# imu_hand.net
KiCad netlist of a schematic drawn in EAGLE
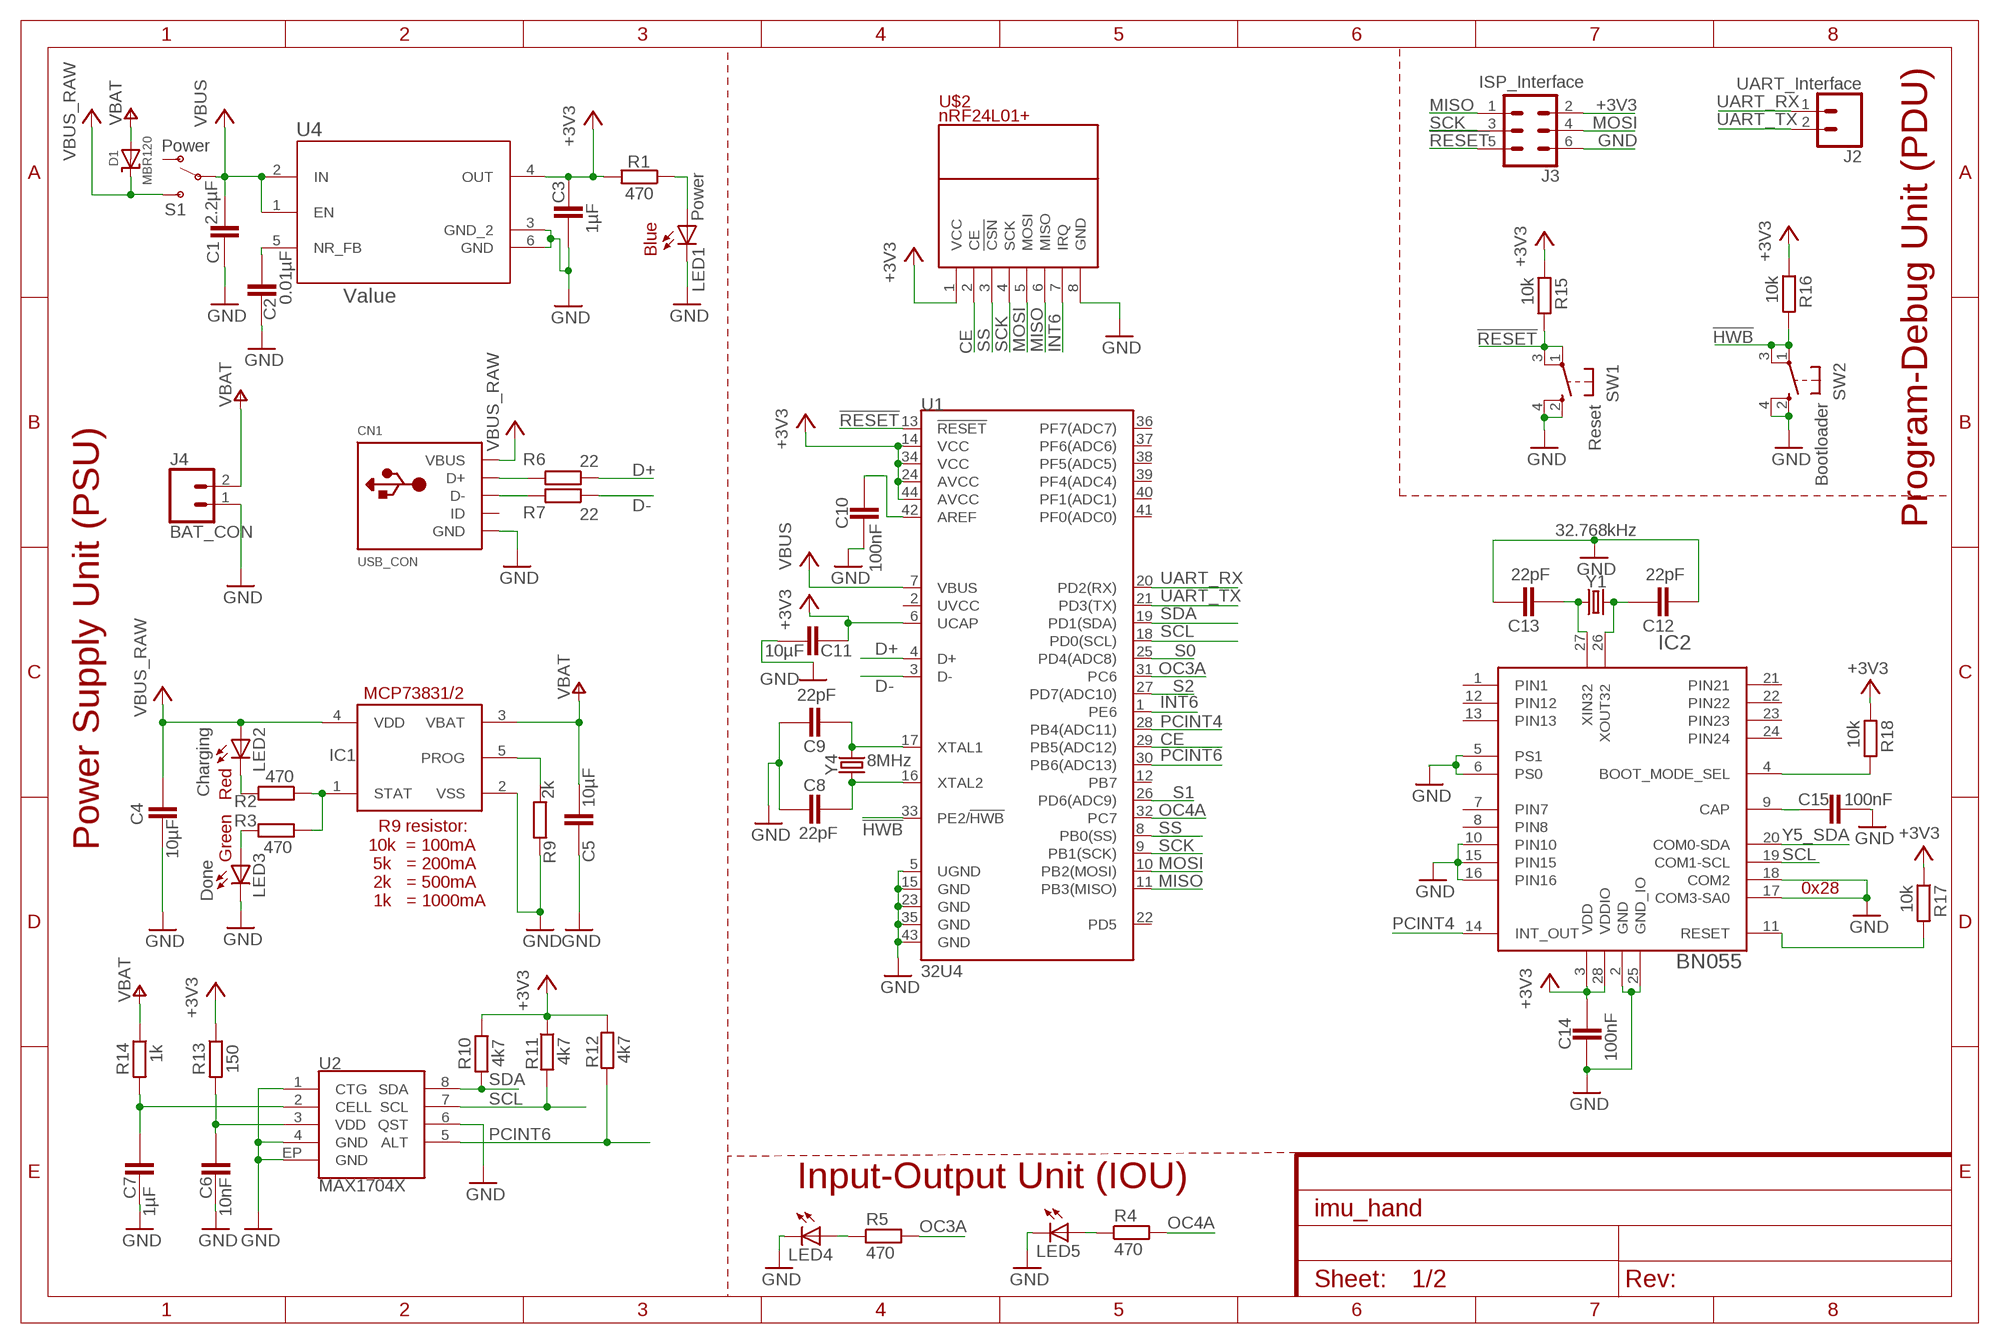
[diagram p0: schematic, sheet 1]
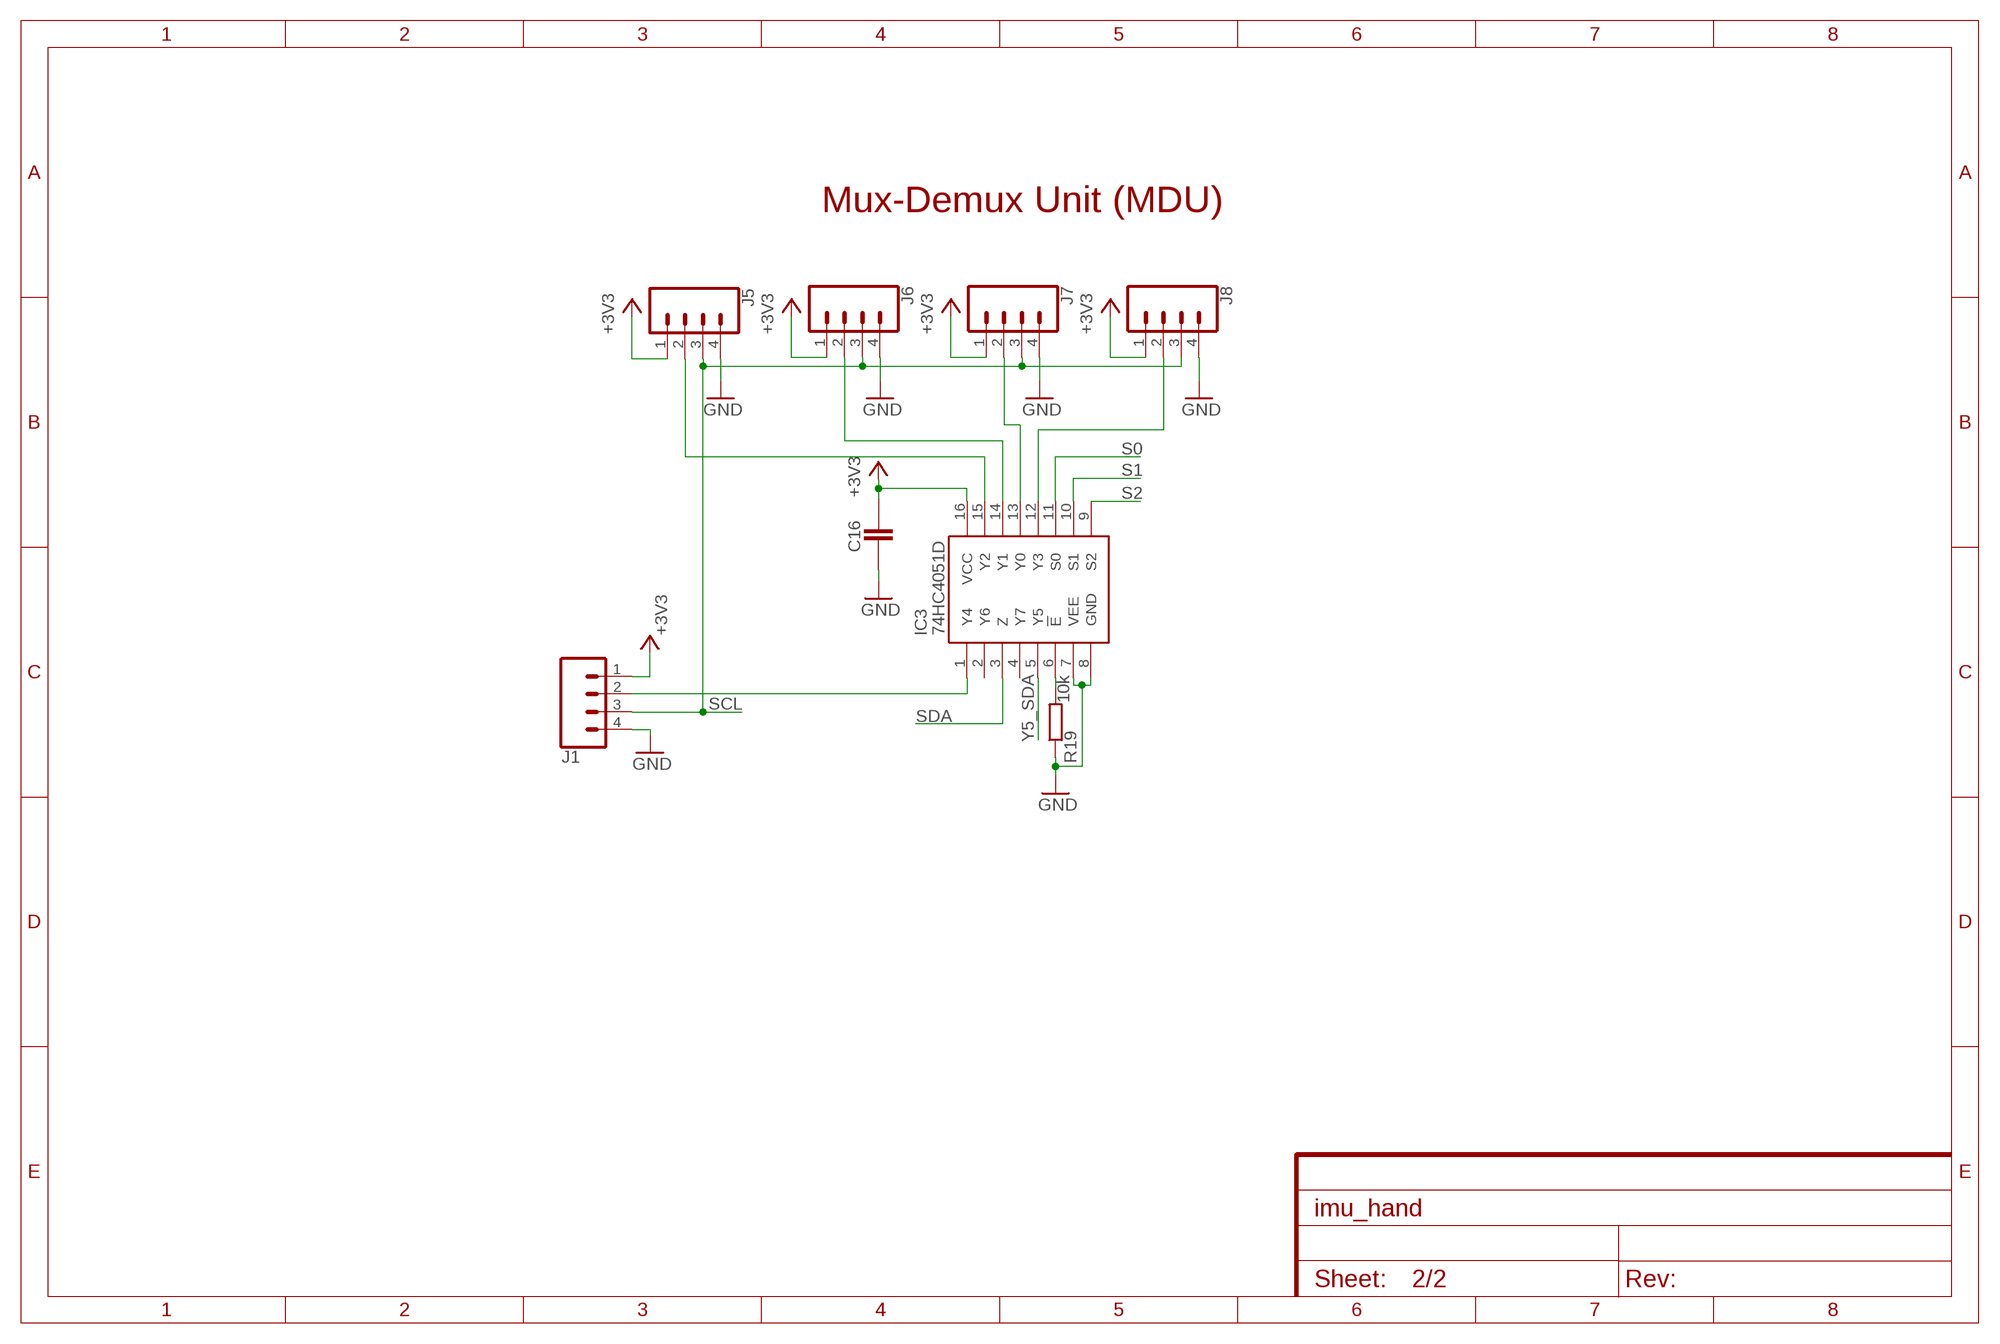
[diagram p1: schematic, sheet 2]

(export (version "E")
  (design (tool "Eeschema 10.0.6"))
  (components
    (comp (ref "C16")
      (value "CAPACITOR_0603")
      (footprint "eagle-import:CAPC1608X92N")
      (libsource (lib "eagle-import") (part "CAPACITOR_0603"))
    )
    (comp (ref "IC3")
      (value "74HC4051D")
      (footprint "eagle-import:SOIC127P600X175-16N")
      (fields (field (name "RS_PART_NUMBER") "1697756P"))
      (libsource (lib "eagle-import") (part "74HC4051D"))
    )
    (comp (ref "J1")
      (value "CONN_04SMD2")
      (footprint "eagle-import:1X04_1MM_RA")
      (libsource (lib "eagle-import") (part "CONN_04SMD2"))
    )
    (comp (ref "J5")
      (value "CONN_04SMD2")
      (footprint "eagle-import:1X04_1MM_RA")
      (libsource (lib "eagle-import") (part "CONN_04SMD2"))
    )
    (comp (ref "J6")
      (value "CONN_04SMD2")
      (footprint "eagle-import:1X04_1MM_RA")
      (libsource (lib "eagle-import") (part "CONN_04SMD2"))
    )
    (comp (ref "J7")
      (value "CONN_04SMD2")
      (footprint "eagle-import:1X04_1MM_RA")
      (libsource (lib "eagle-import") (part "CONN_04SMD2"))
    )
    (comp (ref "J8")
      (value "CONN_04SMD2")
      (footprint "eagle-import:1X04_1MM_RA")
      (libsource (lib "eagle-import") (part "CONN_04SMD2"))
    )
    (comp (ref "R19")
      (value "10k")
      (footprint "eagle-import:RESC1608X55N")
      (libsource (lib "eagle-import") (part "RESISTOR_0603"))
    )
    (comp (ref "C1")
      (value "2.2µF")
      (footprint "eagle-import:CAPC1608X92N")
      (libsource (lib "eagle-import") (part "CAPACITOR_0603"))
    )
    (comp (ref "C2")
      (value "0.01µF")
      (footprint "eagle-import:CAPC1608X92N")
      (libsource (lib "eagle-import") (part "CAPACITOR_0603"))
    )
    (comp (ref "C3")
      (value "1µF")
      (footprint "eagle-import:CAPC1608X92N")
      (libsource (lib "eagle-import") (part "CAPACITOR_0603"))
    )
    (comp (ref "C4")
      (value "10µF")
      (footprint "eagle-import:CAPC1608X92N")
      (libsource (lib "eagle-import") (part "CAPACITOR_0603"))
    )
    (comp (ref "C5")
      (value "10µF")
      (footprint "eagle-import:CAPC1608X92N")
      (libsource (lib "eagle-import") (part "CAPACITOR_0603"))
    )
    (comp (ref "C6")
      (value "10nF")
      (footprint "eagle-import:CAPC1608X92N")
      (libsource (lib "eagle-import") (part "CAPACITOR_0603"))
    )
    (comp (ref "C7")
      (value "1µF")
      (footprint "eagle-import:CAPC1608X92N")
      (libsource (lib "eagle-import") (part "CAPACITOR_0603"))
    )
    (comp (ref "C8")
      (value "22pF")
      (footprint "eagle-import:CAPC1608X92N")
      (libsource (lib "eagle-import") (part "CAPACITOR_0603"))
    )
    (comp (ref "C9")
      (value "22pF")
      (footprint "eagle-import:CAPC1608X92N")
      (libsource (lib "eagle-import") (part "CAPACITOR_0603"))
    )
    (comp (ref "C10")
      (value "100nF")
      (footprint "eagle-import:CAPC1608X92N")
      (libsource (lib "eagle-import") (part "CAPACITOR_0603"))
    )
    (comp (ref "C11")
      (value "10µF")
      (footprint "eagle-import:CAPC1608X92N")
      (libsource (lib "eagle-import") (part "CAPACITOR_0603"))
    )
    (comp (ref "C12")
      (value "22pF")
      (footprint "eagle-import:CAPC1608X92N")
      (libsource (lib "eagle-import") (part "CAPACITOR_0603"))
    )
    (comp (ref "C13")
      (value "22pF")
      (footprint "eagle-import:CAPC1608X92N")
      (libsource (lib "eagle-import") (part "CAPACITOR_0603"))
    )
    (comp (ref "C14")
      (value "100nF")
      (footprint "eagle-import:CAPC1608X92N")
      (libsource (lib "eagle-import") (part "CAPACITOR_0603"))
    )
    (comp (ref "C15")
      (value "100nF")
      (footprint "eagle-import:CAPC1608X92N")
      (libsource (lib "eagle-import") (part "CAPACITOR_0603"))
    )
    (comp (ref "CN1")
      (value "USB_CON")
      (footprint "eagle-import:USB-MINIB")
      (libsource (lib "eagle-import") (part "USBMINIB"))
    )
    (comp (ref "D1")
      (value "MBR120")
      (footprint "eagle-import:SOD-123FL")
      (libsource (lib "eagle-import") (part "DIODE_SOD-123FL"))
    )
    (comp (ref "IC1")
      (value "MCP73831/OT")
      (footprint "eagle-import:SOT23-5L")
      (libsource (lib "eagle-import") (part "MCP73831/OT"))
    )
    (comp (ref "IC2")
      (value "BN055")
      (footprint "eagle-import:LGA-28_3.80X5.20_0.5")
      (fields (field (name "PART_NUMBER") "BNO055"))
      (libsource (lib "eagle-import") (part "1658_BNO055"))
    )
    (comp (ref "J2")
      (value "UART_Interface")
      (footprint "eagle-import:1X02")
      (libsource (lib "eagle-import") (part "CONN_02"))
    )
    (comp (ref "J3")
      (value "ISP_Interface")
      (footprint "eagle-import:2X3")
      (libsource (lib "eagle-import") (part "CONN_03X2FEMALE"))
    )
    (comp (ref "J4")
      (value "BAT_CON")
      (footprint "eagle-import:1X02")
      (libsource (lib "eagle-import") (part "CONN_02"))
    )
    (comp (ref "LED1")
      (value "Power")
      (footprint "eagle-import:CHIPLED_0603")
      (libsource (lib "eagle-import") (part "LEDCHIPLED_0603"))
    )
    (comp (ref "LED2")
      (value "Charging")
      (footprint "eagle-import:CHIPLED_0603")
      (libsource (lib "eagle-import") (part "LEDCHIPLED_0603"))
    )
    (comp (ref "LED3")
      (value "Done")
      (footprint "eagle-import:CHIPLED_0603")
      (libsource (lib "eagle-import") (part "LEDCHIPLED_0603"))
    )
    (comp (ref "LED4")
      (value "LEDCHIPLED_0603")
      (footprint "eagle-import:CHIPLED_0603")
      (libsource (lib "eagle-import") (part "LEDCHIPLED_0603"))
    )
    (comp (ref "LED5")
      (value "LEDCHIPLED_0603")
      (footprint "eagle-import:CHIPLED_0603")
      (libsource (lib "eagle-import") (part "LEDCHIPLED_0603"))
    )
    (comp (ref "R1")
      (value "470")
      (footprint "eagle-import:RESC1608X55N")
      (libsource (lib "eagle-import") (part "RESISTOR_0603"))
    )
    (comp (ref "R2")
      (value "470")
      (footprint "eagle-import:RESC1608X55N")
      (libsource (lib "eagle-import") (part "RESISTOR_0603"))
    )
    (comp (ref "R3")
      (value "470")
      (footprint "eagle-import:RESC1608X55N")
      (libsource (lib "eagle-import") (part "RESISTOR_0603"))
    )
    (comp (ref "R4")
      (value "470")
      (footprint "eagle-import:RESC1608X55N")
      (libsource (lib "eagle-import") (part "RESISTOR_0603"))
    )
    (comp (ref "R5")
      (value "470")
      (footprint "eagle-import:RESC1608X55N")
      (libsource (lib "eagle-import") (part "RESISTOR_0603"))
    )
    (comp (ref "R6")
      (value "22")
      (footprint "eagle-import:RESC1608X55N")
      (libsource (lib "eagle-import") (part "RESISTOR_0603"))
    )
    (comp (ref "R7")
      (value "22")
      (footprint "eagle-import:RESC1608X55N")
      (libsource (lib "eagle-import") (part "RESISTOR_0603"))
    )
    (comp (ref "R9")
      (value "2k")
      (footprint "eagle-import:RESC1608X55N")
      (libsource (lib "eagle-import") (part "RESISTOR_0603"))
    )
    (comp (ref "R10")
      (value "4k7")
      (footprint "eagle-import:RESC1608X55N")
      (libsource (lib "eagle-import") (part "RESISTOR_0603"))
    )
    (comp (ref "R11")
      (value "4k7")
      (footprint "eagle-import:RESC1608X55N")
      (libsource (lib "eagle-import") (part "RESISTOR_0603"))
    )
    (comp (ref "R12")
      (value "4k7")
      (footprint "eagle-import:RESC1608X55N")
      (libsource (lib "eagle-import") (part "RESISTOR_0603"))
    )
    (comp (ref "R13")
      (value "150")
      (footprint "eagle-import:RESC1608X55N")
      (libsource (lib "eagle-import") (part "RESISTOR_0603"))
    )
    (comp (ref "R14")
      (value "1k")
      (footprint "eagle-import:RESC1608X55N")
      (libsource (lib "eagle-import") (part "RESISTOR_0603"))
    )
    (comp (ref "R15")
      (value "10k")
      (footprint "eagle-import:RESC1608X55N")
      (libsource (lib "eagle-import") (part "RESISTOR_0603"))
    )
    (comp (ref "R16")
      (value "10k")
      (footprint "eagle-import:RESC1608X55N")
      (libsource (lib "eagle-import") (part "RESISTOR_0603"))
    )
    (comp (ref "R17")
      (value "10k")
      (footprint "eagle-import:RESC1608X55N")
      (libsource (lib "eagle-import") (part "RESISTOR_0603"))
    )
    (comp (ref "R18")
      (value "10k")
      (footprint "eagle-import:RESC1608X55N")
      (libsource (lib "eagle-import") (part "RESISTOR_0603"))
    )
    (comp (ref "S1")
      (value "Power")
      (footprint "eagle-import:SWITCH_SPDT_PTH_11.6X4.0MM")
      (libsource (lib "eagle-import") (part "SWITCH-SPDT-PTH-11.6X4.0MM"))
    )
    (comp (ref "SW1")
      (value "Reset")
      (footprint "eagle-import:KMR2")
      (libsource (lib "eagle-import") (part "SPST_TACT-KMR2"))
    )
    (comp (ref "SW2")
      (value "Bootloader")
      (footprint "eagle-import:KMR2")
      (libsource (lib "eagle-import") (part "SPST_TACT-KMR2"))
    )
    (comp (ref "U$2")
      (value "nRF24L01+")
      (footprint "eagle-import:6-PIN-BREAKOUT")
      (libsource (lib "eagle-import") (part "6-PIN-BREAKOUT6-PIN-BREAKOUT"))
    )
    (comp (ref "U1")
      (value "32U4")
      (footprint "eagle-import:TQFP44")
      (libsource (lib "eagle-import") (part "ATMEGA32U4TQFP-44"))
    )
    (comp (ref "U2")
      (value "MAX1704X")
      (footprint "eagle-import:TDFN-8")
      (libsource (lib "eagle-import") (part "MAX1704X"))
    )
    (comp (ref "U4")
      (value "Value")
      (footprint "eagle-import:DCQ0006A_N")
      (fields (field (name "MANUFACTURER") "Texas Instruments") (field (name "PARTNUMBER") "TPS79633QDCQRQ1"))
      (libsource (lib "eagle-import") (part "TPS79633QDCQRQ1"))
    )
    (comp (ref "Y1")
      (value "32.768kHz")
      (footprint "eagle-import:CRYSTAL-SMD-3.2X1.5MM")
      (libsource (lib "eagle-import") (part "CRYSTAL-32.768KHZSMD-3.2X1.5"))
    )
    (comp (ref "Y4")
      (value "8MHz")
      (footprint "eagle-import:CRYSTAL-SMD-5X3.2-4PAD")
      (libsource (lib "eagle-import") (part "CRYSTAL-8MHZSMD-5X3.2"))
    )
  )
  (nets
    (net (code "1") (name "+3V3") (class "Default")
      (node (ref "C11") (pin "1") (pinfunction "1_1") (pintype "passive"))
      (node (ref "C14") (pin "1") (pinfunction "1_1") (pintype "passive"))
      (node (ref "C16") (pin "2") (pinfunction "2_2") (pintype "passive"))
      (node (ref "C3") (pin "2") (pinfunction "2_2") (pintype "passive"))
      (node (ref "IC2") (pin "28") (pinfunction "VDDIO_28") (pintype "power_in"))
      (node (ref "IC2") (pin "3") (pinfunction "VDD_3") (pintype "power_in"))
      (node (ref "IC3") (pin "16") (pinfunction "VCC_16") (pintype "bidirectional"))
      (node (ref "J1") (pin "1") (pinfunction "1_1") (pintype "passive"))
      (node (ref "J3") (pin "2") (pinfunction "2_2") (pintype "bidirectional"))
      (node (ref "J5") (pin "1") (pinfunction "1_1") (pintype "passive"))
      (node (ref "J6") (pin "1") (pinfunction "1_1") (pintype "passive"))
      (node (ref "J7") (pin "1") (pinfunction "1_1") (pintype "passive"))
      (node (ref "J8") (pin "1") (pinfunction "1_1") (pintype "passive"))
      (node (ref "R1") (pin "2") (pinfunction "2_2") (pintype "passive"))
      (node (ref "R10") (pin "1") (pinfunction "1_1") (pintype "passive"))
      (node (ref "R11") (pin "1") (pinfunction "1_1") (pintype "passive"))
      (node (ref "R12") (pin "1") (pinfunction "1_1") (pintype "passive"))
      (node (ref "R13") (pin "1") (pinfunction "1_1") (pintype "passive"))
      (node (ref "R15") (pin "1") (pinfunction "1_1") (pintype "passive"))
      (node (ref "R16") (pin "1") (pinfunction "1_1") (pintype "passive"))
      (node (ref "R17") (pin "1") (pinfunction "1_1") (pintype "passive"))
      (node (ref "R18") (pin "1") (pinfunction "1_1") (pintype "passive"))
      (node (ref "U$2") (pin "1") (pinfunction "VCC_1") (pintype "bidirectional"))
      (node (ref "U1") (pin "14") (pinfunction "VCC_14") (pintype "bidirectional"))
      (node (ref "U1") (pin "24") (pinfunction "AVCC_24") (pintype "bidirectional"))
      (node (ref "U1") (pin "34") (pinfunction "VCC_34") (pintype "bidirectional"))
      (node (ref "U1") (pin "44") (pinfunction "AVCC_44") (pintype "bidirectional"))
      (node (ref "U1") (pin "6") (pinfunction "UCAP_6") (pintype "bidirectional"))
      (node (ref "U4") (pin "4") (pinfunction "OUT_4") (pintype "power_in"))
    )
    (net (code "2") (name "CE") (class "Default")
      (node (ref "U$2") (pin "2") (pinfunction "CE_2") (pintype "bidirectional"))
      (node (ref "U1") (pin "29") (pinfunction "PB5(ADC12)_29") (pintype "bidirectional"))
    )
    (net (code "3") (name "D+") (class "Default")
      (node (ref "R6") (pin "1") (pinfunction "1_1") (pintype "passive"))
      (node (ref "U1") (pin "4") (pinfunction "D+_4") (pintype "bidirectional"))
    )
    (net (code "4") (name "D-") (class "Default")
      (node (ref "R7") (pin "1") (pinfunction "1_1") (pintype "passive"))
      (node (ref "U1") (pin "3") (pinfunction "D-_3") (pintype "bidirectional"))
    )
    (net (code "5") (name "GND") (class "Default")
      (node (ref "C1") (pin "1") (pinfunction "1_1") (pintype "passive"))
      (node (ref "C10") (pin "2") (pinfunction "2_2") (pintype "passive"))
      (node (ref "C11") (pin "2") (pinfunction "2_2") (pintype "passive"))
      (node (ref "C12") (pin "1") (pinfunction "1_1") (pintype "passive"))
      (node (ref "C13") (pin "2") (pinfunction "2_2") (pintype "passive"))
      (node (ref "C14") (pin "2") (pinfunction "2_2") (pintype "passive"))
      (node (ref "C15") (pin "2") (pinfunction "2_2") (pintype "passive"))
      (node (ref "C16") (pin "1") (pinfunction "1_1") (pintype "passive"))
      (node (ref "C2") (pin "1") (pinfunction "1_1") (pintype "passive"))
      (node (ref "C3") (pin "1") (pinfunction "1_1") (pintype "passive"))
      (node (ref "C4") (pin "1") (pinfunction "1_1") (pintype "passive"))
      (node (ref "C5") (pin "1") (pinfunction "1_1") (pintype "passive"))
      (node (ref "C6") (pin "1") (pinfunction "1_1") (pintype "passive"))
      (node (ref "C7") (pin "1") (pinfunction "1_1") (pintype "passive"))
      (node (ref "C8") (pin "2") (pinfunction "2_2") (pintype "passive"))
      (node (ref "C9") (pin "2") (pinfunction "2_2") (pintype "passive"))
      (node (ref "CN1") (pin "GND") (pinfunction "GND_GND") (pintype "power_in"))
      (node (ref "IC1") (pin "2") (pinfunction "VSS_2") (pintype "power_in"))
      (node (ref "IC2") (pin "10") (pinfunction "PIN10_10") (pintype "passive"))
      (node (ref "IC2") (pin "15") (pinfunction "PIN15_15") (pintype "passive"))
      (node (ref "IC2") (pin "16") (pinfunction "PIN16_16") (pintype "passive"))
      (node (ref "IC2") (pin "17") (pinfunction "COM3-SA0_17") (pintype "bidirectional"))
      (node (ref "IC2") (pin "18") (pinfunction "COM2_18") (pintype "bidirectional"))
      (node (ref "IC2") (pin "2") (pinfunction "GND_2") (pintype "power_in"))
      (node (ref "IC2") (pin "25") (pinfunction "GND_IO_25") (pintype "power_in"))
      (node (ref "IC2") (pin "5") (pinfunction "PS1_5") (pintype "input"))
      (node (ref "IC2") (pin "6") (pinfunction "PS0_6") (pintype "input"))
      (node (ref "IC3") (pin "7") (pinfunction "VEE_7") (pintype "bidirectional"))
      (node (ref "IC3") (pin "8") (pinfunction "GND_8") (pintype "bidirectional"))
      (node (ref "J1") (pin "4") (pinfunction "4_4") (pintype "passive"))
      (node (ref "J3") (pin "6") (pinfunction "6_6") (pintype "bidirectional"))
      (node (ref "J4") (pin "1") (pinfunction "1_1") (pintype "passive"))
      (node (ref "J5") (pin "4") (pinfunction "4_4") (pintype "passive"))
      (node (ref "J6") (pin "4") (pinfunction "4_4") (pintype "passive"))
      (node (ref "J7") (pin "4") (pinfunction "4_4") (pintype "passive"))
      (node (ref "J8") (pin "4") (pinfunction "4_4") (pintype "passive"))
      (node (ref "LED1") (pin "C") (pinfunction "C_C") (pintype "passive"))
      (node (ref "LED3") (pin "C") (pinfunction "C_C") (pintype "passive"))
      (node (ref "LED4") (pin "C") (pinfunction "C_C") (pintype "passive"))
      (node (ref "LED5") (pin "C") (pinfunction "C_C") (pintype "passive"))
      (node (ref "R19") (pin "1") (pinfunction "1_1") (pintype "passive"))
      (node (ref "R9") (pin "2") (pinfunction "2_2") (pintype "passive"))
      (node (ref "SW1") (pin "2") (pinfunction "S_2") (pintype "passive"))
      (node (ref "SW1") (pin "4") (pinfunction "S1_4") (pintype "passive"))
      (node (ref "SW2") (pin "2") (pinfunction "S_2") (pintype "passive"))
      (node (ref "SW2") (pin "4") (pinfunction "S1_4") (pintype "passive"))
      (node (ref "U$2") (pin "8") (pinfunction "GND_8") (pintype "bidirectional"))
      (node (ref "U1") (pin "15") (pinfunction "GND_15") (pintype "bidirectional"))
      (node (ref "U1") (pin "23") (pinfunction "GND_23") (pintype "bidirectional"))
      (node (ref "U1") (pin "35") (pinfunction "GND_35") (pintype "bidirectional"))
      (node (ref "U1") (pin "43") (pinfunction "GND_43") (pintype "bidirectional"))
      (node (ref "U1") (pin "5") (pinfunction "UGND_5") (pintype "bidirectional"))
      (node (ref "U2") (pin "1") (pinfunction "CTG_1") (pintype "bidirectional"))
      (node (ref "U2") (pin "4") (pinfunction "GND_4") (pintype "bidirectional"))
      (node (ref "U2") (pin "6") (pinfunction "QST_6") (pintype "bidirectional"))
      (node (ref "U2") (pin "EP") (pinfunction "GND_EP") (pintype "bidirectional"))
      (node (ref "U4") (pin "3") (pinfunction "GND_2_3") (pintype "power_in"))
      (node (ref "U4") (pin "6") (pinfunction "GND_6") (pintype "power_in"))
    )
    (net (code "6") (name "INT6") (class "Default")
      (node (ref "U$2") (pin "7") (pinfunction "IRQ_7") (pintype "bidirectional"))
      (node (ref "U1") (pin "1") (pinfunction "PE6_1") (pintype "bidirectional"))
    )
    (net (code "7") (name "MISO") (class "Default")
      (node (ref "J3") (pin "1") (pinfunction "1_1") (pintype "bidirectional"))
      (node (ref "U$2") (pin "6") (pinfunction "MISO_6") (pintype "bidirectional"))
      (node (ref "U1") (pin "11") (pinfunction "PB3(MISO)_11") (pintype "bidirectional"))
    )
    (net (code "8") (name "MOSI") (class "Default")
      (node (ref "J3") (pin "4") (pinfunction "4_4") (pintype "bidirectional"))
      (node (ref "U$2") (pin "5") (pinfunction "MOSI_5") (pintype "bidirectional"))
      (node (ref "U1") (pin "10") (pinfunction "PB2(MOSI)_10") (pintype "bidirectional"))
    )
    (net (code "9") (name "Net-(CN1-PadD+)") (class "Default")
      (node (ref "CN1") (pin "D+") (pinfunction "D+_D+") (pintype "bidirectional"))
      (node (ref "R6") (pin "2") (pinfunction "2_2") (pintype "passive"))
    )
    (net (code "10") (name "Net-(CN1-PadD-)") (class "Default")
      (node (ref "CN1") (pin "D-") (pinfunction "D-_D-") (pintype "bidirectional"))
      (node (ref "R7") (pin "2") (pinfunction "2_2") (pintype "passive"))
    )
    (net (code "11") (name "Net-(IC1-PROG)") (class "Default")
      (node (ref "IC1") (pin "5") (pinfunction "PROG_5") (pintype "input"))
      (node (ref "R9") (pin "1") (pinfunction "1_1") (pintype "passive"))
    )
    (net (code "12") (name "Net-(IC1-STAT)") (class "Default")
      (node (ref "IC1") (pin "1") (pinfunction "STAT_1") (pintype "output"))
      (node (ref "R2") (pin "1") (pinfunction "1_1") (pintype "passive"))
      (node (ref "R3") (pin "1") (pinfunction "1_1") (pintype "passive"))
    )
    (net (code "13") (name "Net-(IC2-BOOT_MODE_SEL)") (class "Default")
      (node (ref "IC2") (pin "4") (pinfunction "BOOT_MODE_SEL_4") (pintype "input"))
      (node (ref "R18") (pin "2") (pinfunction "2_2") (pintype "passive"))
    )
    (net (code "14") (name "Net-(IC2-CAP)") (class "Default")
      (node (ref "C15") (pin "1") (pinfunction "1_1") (pintype "passive"))
      (node (ref "IC2") (pin "9") (pinfunction "CAP_9") (pintype "tri_state"))
    )
    (net (code "15") (name "Net-(IC2-RESET)") (class "Default")
      (node (ref "IC2") (pin "11") (pinfunction "RESET_11") (pintype "input"))
      (node (ref "R17") (pin "2") (pinfunction "2_2") (pintype "passive"))
    )
    (net (code "16") (name "Net-(IC2-XIN32)") (class "Default")
      (node (ref "C13") (pin "1") (pinfunction "1_1") (pintype "passive"))
      (node (ref "IC2") (pin "27") (pinfunction "XIN32_27") (pintype "bidirectional"))
      (node (ref "Y1") (pin "P$1") (pinfunction "1_P$1") (pintype "passive"))
    )
    (net (code "17") (name "Net-(IC2-XOUT32)") (class "Default")
      (node (ref "C12") (pin "2") (pinfunction "2_2") (pintype "passive"))
      (node (ref "IC2") (pin "26") (pinfunction "XOUT32_26") (pintype "output"))
      (node (ref "Y1") (pin "P$2") (pinfunction "2_P$2") (pintype "passive"))
    )
    (net (code "18") (name "Net-(IC3-Y0)") (class "Default")
      (node (ref "IC3") (pin "13") (pinfunction "Y0_13") (pintype "bidirectional"))
      (node (ref "J7") (pin "2") (pinfunction "2_2") (pintype "passive"))
    )
    (net (code "19") (name "Net-(IC3-Y1)") (class "Default")
      (node (ref "IC3") (pin "14") (pinfunction "Y1_14") (pintype "bidirectional"))
      (node (ref "J6") (pin "2") (pinfunction "2_2") (pintype "passive"))
    )
    (net (code "20") (name "Net-(IC3-Y2)") (class "Default")
      (node (ref "IC3") (pin "15") (pinfunction "Y2_15") (pintype "bidirectional"))
      (node (ref "J5") (pin "2") (pinfunction "2_2") (pintype "passive"))
    )
    (net (code "21") (name "Net-(IC3-Y3)") (class "Default")
      (node (ref "IC3") (pin "12") (pinfunction "Y3_12") (pintype "bidirectional"))
      (node (ref "J8") (pin "2") (pinfunction "2_2") (pintype "passive"))
    )
    (net (code "22") (name "Net-(IC3-Y4)") (class "Default")
      (node (ref "IC3") (pin "1") (pinfunction "Y4_1") (pintype "bidirectional"))
      (node (ref "J1") (pin "2") (pinfunction "2_2") (pintype "passive"))
    )
    (net (code "23") (name "Net-(IC3-~{E})") (class "Default")
      (node (ref "IC3") (pin "6") (pinfunction "~{E}_6") (pintype "bidirectional"))
      (node (ref "R19") (pin "2") (pinfunction "2_2") (pintype "passive"))
    )
    (net (code "24") (name "Net-(LED1-PadA)") (class "Default")
      (node (ref "LED1") (pin "A") (pinfunction "A_A") (pintype "passive"))
      (node (ref "R1") (pin "1") (pinfunction "1_1") (pintype "passive"))
    )
    (net (code "25") (name "Net-(LED2-PadC)") (class "Default")
      (node (ref "LED2") (pin "C") (pinfunction "C_C") (pintype "passive"))
      (node (ref "R2") (pin "2") (pinfunction "2_2") (pintype "passive"))
    )
    (net (code "26") (name "Net-(LED3-PadA)") (class "Default")
      (node (ref "LED3") (pin "A") (pinfunction "A_A") (pintype "passive"))
      (node (ref "R3") (pin "2") (pinfunction "2_2") (pintype "passive"))
    )
    (net (code "27") (name "Net-(LED4-PadA)") (class "Default")
      (node (ref "LED4") (pin "A") (pinfunction "A_A") (pintype "passive"))
      (node (ref "R5") (pin "1") (pinfunction "1_1") (pintype "passive"))
    )
    (net (code "28") (name "Net-(LED5-PadA)") (class "Default")
      (node (ref "LED5") (pin "A") (pinfunction "A_A") (pintype "passive"))
      (node (ref "R4") (pin "1") (pinfunction "1_1") (pintype "passive"))
    )
    (net (code "29") (name "Net-(U1-AREF)") (class "Default")
      (node (ref "C10") (pin "1") (pinfunction "1_1") (pintype "passive"))
      (node (ref "U1") (pin "42") (pinfunction "AREF_42") (pintype "bidirectional"))
    )
    (net (code "30") (name "Net-(U1-XTAL1)") (class "Default")
      (node (ref "C9") (pin "1") (pinfunction "1_1") (pintype "passive"))
      (node (ref "U1") (pin "17") (pinfunction "XTAL1_17") (pintype "bidirectional"))
      (node (ref "Y4") (pin "3") (pinfunction "2_3") (pintype "passive"))
    )
    (net (code "31") (name "Net-(U1-XTAL2)") (class "Default")
      (node (ref "C8") (pin "1") (pinfunction "1_1") (pintype "passive"))
      (node (ref "U1") (pin "16") (pinfunction "XTAL2_16") (pintype "bidirectional"))
      (node (ref "Y4") (pin "1") (pinfunction "1_1") (pintype "passive"))
    )
    (net (code "32") (name "Net-(U2-CELL)") (class "Default")
      (node (ref "C7") (pin "2") (pinfunction "2_2") (pintype "passive"))
      (node (ref "R14") (pin "2") (pinfunction "2_2") (pintype "passive"))
      (node (ref "U2") (pin "2") (pinfunction "CELL_2") (pintype "bidirectional"))
    )
    (net (code "33") (name "Net-(U2-VDD)") (class "Default")
      (node (ref "C6") (pin "2") (pinfunction "2_2") (pintype "passive"))
      (node (ref "R13") (pin "2") (pinfunction "2_2") (pintype "passive"))
      (node (ref "U2") (pin "3") (pinfunction "VDD_3") (pintype "bidirectional"))
    )
    (net (code "34") (name "Net-(U4-NR_FB)") (class "Default")
      (node (ref "C2") (pin "2") (pinfunction "2_2") (pintype "passive"))
      (node (ref "U4") (pin "5") (pinfunction "NR_FB_5") (pintype "passive"))
    )
    (net (code "35") (name "OC3A") (class "Default")
      (node (ref "R5") (pin "2") (pinfunction "2_2") (pintype "passive"))
      (node (ref "U1") (pin "31") (pinfunction "PC6_31") (pintype "bidirectional"))
    )
    (net (code "36") (name "OC4A") (class "Default")
      (node (ref "R4") (pin "2") (pinfunction "2_2") (pintype "passive"))
      (node (ref "U1") (pin "32") (pinfunction "PC7_32") (pintype "bidirectional"))
    )
    (net (code "37") (name "PCINT4") (class "Default")
      (node (ref "IC2") (pin "14") (pinfunction "INT_OUT_14") (pintype "output"))
      (node (ref "U1") (pin "28") (pinfunction "PB4(ADC11)_28") (pintype "bidirectional"))
    )
    (net (code "38") (name "PCINT6") (class "Default")
      (node (ref "R12") (pin "2") (pinfunction "2_2") (pintype "passive"))
      (node (ref "U1") (pin "30") (pinfunction "PB6(ADC13)_30") (pintype "bidirectional"))
      (node (ref "U2") (pin "5") (pinfunction "ALT_5") (pintype "bidirectional"))
    )
    (net (code "39") (name "S0") (class "Default")
      (node (ref "IC3") (pin "11") (pinfunction "S0_11") (pintype "bidirectional"))
      (node (ref "U1") (pin "25") (pinfunction "PD4(ADC8)_25") (pintype "bidirectional"))
    )
    (net (code "40") (name "S1") (class "Default")
      (node (ref "IC3") (pin "10") (pinfunction "S1_10") (pintype "bidirectional"))
      (node (ref "U1") (pin "26") (pinfunction "PD6(ADC9)_26") (pintype "bidirectional"))
    )
    (net (code "41") (name "S2") (class "Default")
      (node (ref "IC3") (pin "9") (pinfunction "S2_9") (pintype "bidirectional"))
      (node (ref "U1") (pin "27") (pinfunction "PD7(ADC10)_27") (pintype "bidirectional"))
    )
    (net (code "42") (name "SCK") (class "Default")
      (node (ref "J3") (pin "3") (pinfunction "3_3") (pintype "bidirectional"))
      (node (ref "U$2") (pin "4") (pinfunction "SCK_4") (pintype "bidirectional"))
      (node (ref "U1") (pin "9") (pinfunction "PB1(SCK)_9") (pintype "bidirectional"))
    )
    (net (code "43") (name "SCL") (class "Default")
      (node (ref "IC2") (pin "19") (pinfunction "COM1-SCL_19") (pintype "bidirectional"))
      (node (ref "J1") (pin "3") (pinfunction "3_3") (pintype "passive"))
      (node (ref "J5") (pin "3") (pinfunction "3_3") (pintype "passive"))
      (node (ref "J6") (pin "3") (pinfunction "3_3") (pintype "passive"))
      (node (ref "J7") (pin "3") (pinfunction "3_3") (pintype "passive"))
      (node (ref "J8") (pin "3") (pinfunction "3_3") (pintype "passive"))
      (node (ref "R11") (pin "2") (pinfunction "2_2") (pintype "passive"))
      (node (ref "U1") (pin "18") (pinfunction "PD0(SCL)_18") (pintype "bidirectional"))
      (node (ref "U2") (pin "7") (pinfunction "SCL_7") (pintype "bidirectional"))
    )
    (net (code "44") (name "SDA") (class "Default")
      (node (ref "IC3") (pin "3") (pinfunction "Z_3") (pintype "bidirectional"))
      (node (ref "R10") (pin "2") (pinfunction "2_2") (pintype "passive"))
      (node (ref "U1") (pin "19") (pinfunction "PD1(SDA)_19") (pintype "bidirectional"))
      (node (ref "U2") (pin "8") (pinfunction "SDA_8") (pintype "bidirectional"))
    )
    (net (code "45") (name "SS") (class "Default")
      (node (ref "U$2") (pin "3") (pinfunction "~{CSN}_3") (pintype "bidirectional"))
      (node (ref "U1") (pin "8") (pinfunction "PB0(SS)_8") (pintype "bidirectional"))
    )
    (net (code "46") (name "UART_RX") (class "Default")
      (node (ref "J2") (pin "1") (pinfunction "1_1") (pintype "passive"))
      (node (ref "U1") (pin "20") (pinfunction "PD2(RX)_20") (pintype "bidirectional"))
    )
    (net (code "47") (name "UART_TX") (class "Default")
      (node (ref "J2") (pin "2") (pinfunction "2_2") (pintype "passive"))
      (node (ref "U1") (pin "21") (pinfunction "PD3(TX)_21") (pintype "bidirectional"))
    )
    (net (code "48") (name "VBAT") (class "Default")
      (node (ref "C5") (pin "2") (pinfunction "2_2") (pintype "passive"))
      (node (ref "D1") (pin "A") (pinfunction "A_A") (pintype "passive"))
      (node (ref "IC1") (pin "3") (pinfunction "VBAT_3") (pintype "bidirectional"))
      (node (ref "J4") (pin "2") (pinfunction "2_2") (pintype "passive"))
      (node (ref "R14") (pin "1") (pinfunction "1_1") (pintype "passive"))
    )
    (net (code "49") (name "VBUS") (class "Default")
      (node (ref "C1") (pin "2") (pinfunction "2_2") (pintype "passive"))
      (node (ref "S1") (pin "2") (pinfunction "P_2") (pintype "passive"))
      (node (ref "U1") (pin "7") (pinfunction "VBUS_7") (pintype "bidirectional"))
      (node (ref "U4") (pin "1") (pinfunction "EN_1") (pintype "input"))
      (node (ref "U4") (pin "2") (pinfunction "IN_2") (pintype "power_in"))
    )
    (net (code "50") (name "VBUS_RAW") (class "Default")
      (node (ref "C4") (pin "2") (pinfunction "2_2") (pintype "passive"))
      (node (ref "CN1") (pin "VBUS") (pinfunction "VBUS_VBUS") (pintype "power_in"))
      (node (ref "D1") (pin "C") (pinfunction "C_C") (pintype "passive"))
      (node (ref "IC1") (pin "4") (pinfunction "VDD_4") (pintype "power_in"))
      (node (ref "LED2") (pin "A") (pinfunction "A_A") (pintype "passive"))
      (node (ref "S1") (pin "3") (pinfunction "S_3") (pintype "passive"))
    )
    (net (code "51") (name "Y5_SDA") (class "Default")
      (node (ref "IC2") (pin "20") (pinfunction "COM0-SDA_20") (pintype "bidirectional"))
      (node (ref "IC3") (pin "5") (pinfunction "Y5_5") (pintype "bidirectional"))
    )
    (net (code "52") (name "unconnected-(CN1-PadID)") (class "Default")
      (node (ref "CN1") (pin "ID") (pinfunction "ID_ID") (pintype "bidirectional"))
    )
    (net (code "53") (name "unconnected-(IC2-PIN1-Pad1)") (class "Default")
      (node (ref "IC2") (pin "1") (pinfunction "PIN1_1") (pintype "no_connect"))
    )
    (net (code "54") (name "unconnected-(IC2-PIN7-Pad7)") (class "Default")
      (node (ref "IC2") (pin "7") (pinfunction "PIN7_7") (pintype "tri_state"))
    )
    (net (code "55") (name "unconnected-(IC2-PIN8-Pad8)") (class "Default")
      (node (ref "IC2") (pin "8") (pinfunction "PIN8_8") (pintype "tri_state"))
    )
    (net (code "56") (name "unconnected-(IC2-PIN12-Pad12)") (class "Default")
      (node (ref "IC2") (pin "12") (pinfunction "PIN12_12") (pintype "passive"))
    )
    (net (code "57") (name "unconnected-(IC2-PIN13-Pad13)") (class "Default")
      (node (ref "IC2") (pin "13") (pinfunction "PIN13_13") (pintype "passive"))
    )
    (net (code "58") (name "unconnected-(IC2-PIN21-Pad21)") (class "Default")
      (node (ref "IC2") (pin "21") (pinfunction "PIN21_21") (pintype "passive"))
    )
    (net (code "59") (name "unconnected-(IC2-PIN22-Pad22)") (class "Default")
      (node (ref "IC2") (pin "22") (pinfunction "PIN22_22") (pintype "passive"))
    )
    (net (code "60") (name "unconnected-(IC2-PIN23-Pad23)") (class "Default")
      (node (ref "IC2") (pin "23") (pinfunction "PIN23_23") (pintype "passive"))
    )
    (net (code "61") (name "unconnected-(IC2-PIN24-Pad24)") (class "Default")
      (node (ref "IC2") (pin "24") (pinfunction "PIN24_24") (pintype "passive"))
    )
    (net (code "62") (name "unconnected-(IC3-Y6-Pad2)") (class "Default")
      (node (ref "IC3") (pin "2") (pinfunction "Y6_2") (pintype "bidirectional"))
    )
    (net (code "63") (name "unconnected-(IC3-Y7-Pad4)") (class "Default")
      (node (ref "IC3") (pin "4") (pinfunction "Y7_4") (pintype "bidirectional"))
    )
    (net (code "64") (name "unconnected-(S1-O-Pad1)") (class "Default")
      (node (ref "S1") (pin "1") (pinfunction "O_1") (pintype "passive"))
    )
    (net (code "65") (name "unconnected-(U1-PB7-Pad12)") (class "Default")
      (node (ref "U1") (pin "12") (pinfunction "PB7_12") (pintype "bidirectional"))
    )
    (net (code "66") (name "unconnected-(U1-PD5-Pad22)") (class "Default")
      (node (ref "U1") (pin "22") (pinfunction "PD5_22") (pintype "bidirectional"))
    )
    (net (code "67") (name "unconnected-(U1-PF0(ADC0)-Pad41)") (class "Default")
      (node (ref "U1") (pin "41") (pinfunction "PF0(ADC0)_41") (pintype "bidirectional"))
    )
    (net (code "68") (name "unconnected-(U1-PF1(ADC1)-Pad40)") (class "Default")
      (node (ref "U1") (pin "40") (pinfunction "PF1(ADC1)_40") (pintype "bidirectional"))
    )
    (net (code "69") (name "unconnected-(U1-PF4(ADC4)-Pad39)") (class "Default")
      (node (ref "U1") (pin "39") (pinfunction "PF4(ADC4)_39") (pintype "bidirectional"))
    )
    (net (code "70") (name "unconnected-(U1-PF5(ADC5)-Pad38)") (class "Default")
      (node (ref "U1") (pin "38") (pinfunction "PF5(ADC5)_38") (pintype "bidirectional"))
    )
    (net (code "71") (name "unconnected-(U1-PF6(ADC6)-Pad37)") (class "Default")
      (node (ref "U1") (pin "37") (pinfunction "PF6(ADC6)_37") (pintype "bidirectional"))
    )
    (net (code "72") (name "unconnected-(U1-PF7(ADC7)-Pad36)") (class "Default")
      (node (ref "U1") (pin "36") (pinfunction "PF7(ADC7)_36") (pintype "bidirectional"))
    )
    (net (code "73") (name "unconnected-(U1-UVCC-Pad2)") (class "Default")
      (node (ref "U1") (pin "2") (pinfunction "UVCC_2") (pintype "bidirectional"))
    )
    (net (code "74") (name "~{HWB}") (class "Default")
      (node (ref "R16") (pin "2") (pinfunction "2_2") (pintype "passive"))
      (node (ref "SW2") (pin "1") (pinfunction "P_1") (pintype "passive"))
      (node (ref "SW2") (pin "3") (pinfunction "P1_3") (pintype "passive"))
      (node (ref "U1") (pin "33") (pinfunction "PE2/~{HWB}_33") (pintype "bidirectional"))
    )
    (net (code "75") (name "~{RESET}") (class "Default")
      (node (ref "J3") (pin "5") (pinfunction "5_5") (pintype "bidirectional"))
      (node (ref "R15") (pin "2") (pinfunction "2_2") (pintype "passive"))
      (node (ref "SW1") (pin "1") (pinfunction "P_1") (pintype "passive"))
      (node (ref "SW1") (pin "3") (pinfunction "P1_3") (pintype "passive"))
      (node (ref "U1") (pin "13") (pinfunction "~{RESET}_13") (pintype "bidirectional"))
    )
  )
)
